# IO_Carte_Nucleo.net
KiCad netlist of a schematic drawn in Altium Designer
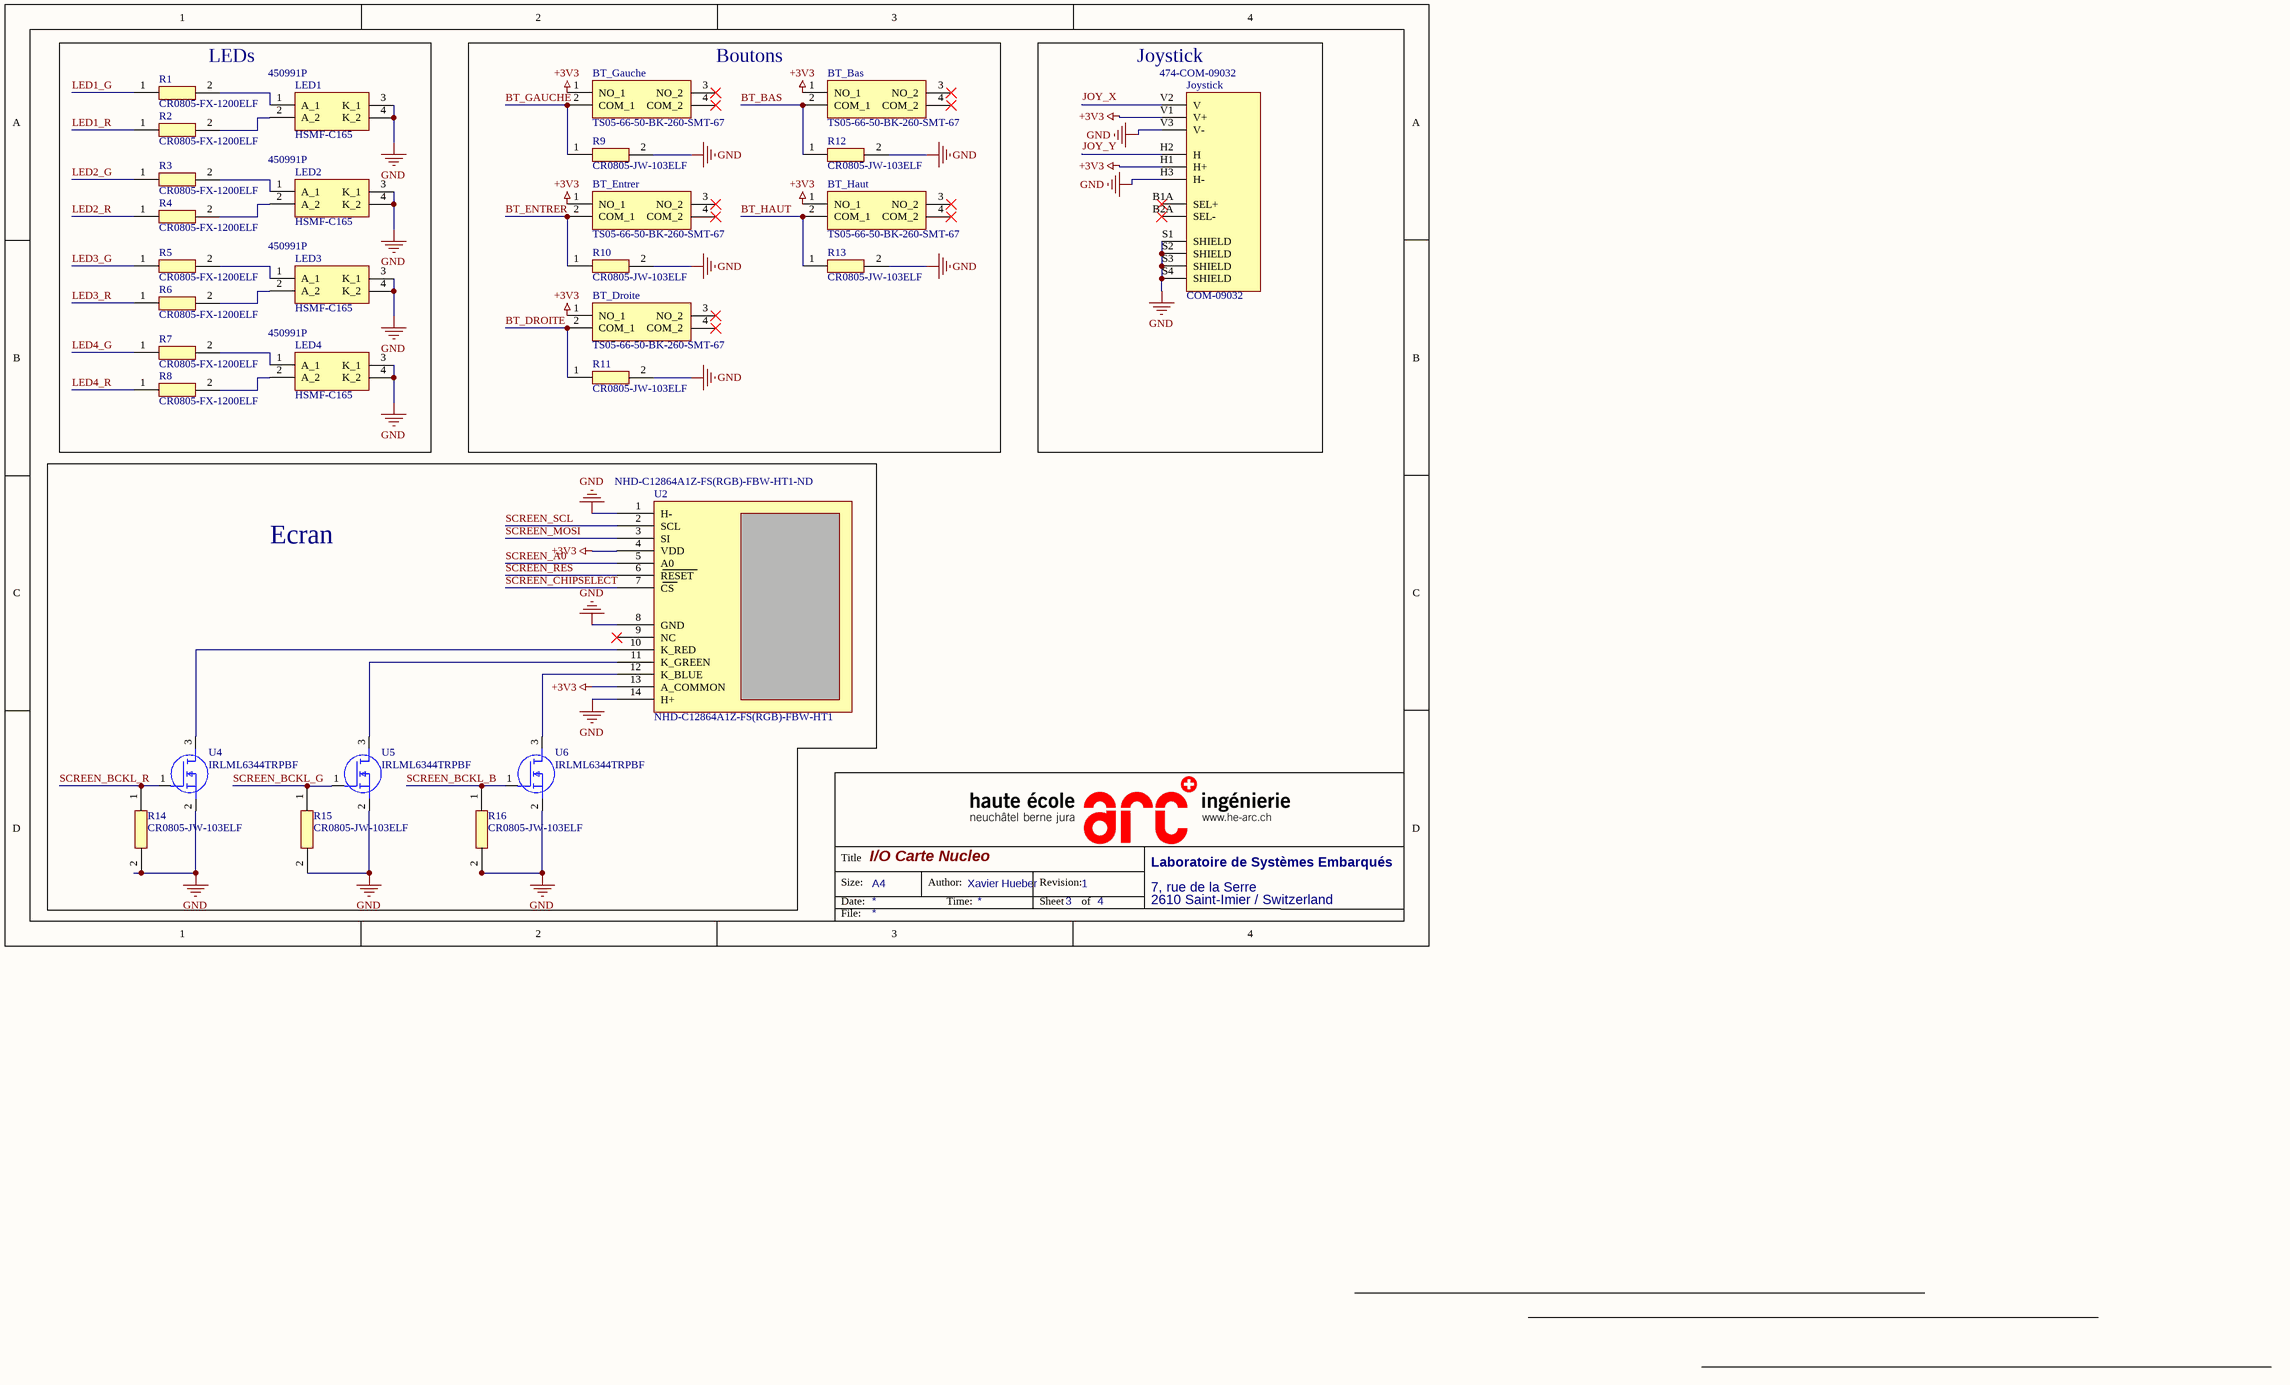
[diagram p0: IO_Carte_Nucleo.SchDoc]

(export (version "E")
  (design (tool "Eeschema 10.0.6"))
  (components
    (comp (ref "BT_Bas")
      (value "TS05-66-50-BK-260-SMT-67")
      (footprint "SamacSys:TS056650BK260SMT67")
      (description "6 x 6 mm, 4.3 ~ 8 mm Actuator Height, 100 ~ 260 gf, Surface Mount, IP67, SPST, Tactile Switch")
      (libsource (lib "*") (part "TS05-66-50-BK-260-SMT-67"))
    )
    (comp (ref "BT_Droite")
      (value "TS05-66-50-BK-260-SMT-67")
      (footprint "SamacSys:TS056650BK260SMT67")
      (description "6 x 6 mm, 4.3 ~ 8 mm Actuator Height, 100 ~ 260 gf, Surface Mount, IP67, SPST, Tactile Switch")
      (libsource (lib "*") (part "TS05-66-50-BK-260-SMT-67"))
    )
    (comp (ref "BT_Entrer")
      (value "TS05-66-50-BK-260-SMT-67")
      (footprint "SamacSys:TS056650BK260SMT67")
      (description "6 x 6 mm, 4.3 ~ 8 mm Actuator Height, 100 ~ 260 gf, Surface Mount, IP67, SPST, Tactile Switch")
      (libsource (lib "*") (part "TS05-66-50-BK-260-SMT-67"))
    )
    (comp (ref "BT_Gauche")
      (value "TS05-66-50-BK-260-SMT-67")
      (footprint "SamacSys:TS056650BK260SMT67")
      (description "6 x 6 mm, 4.3 ~ 8 mm Actuator Height, 100 ~ 260 gf, Surface Mount, IP67, SPST, Tactile Switch")
      (libsource (lib "*") (part "TS05-66-50-BK-260-SMT-67"))
    )
    (comp (ref "BT_Haut")
      (value "TS05-66-50-BK-260-SMT-67")
      (footprint "SamacSys:TS056650BK260SMT67")
      (description "6 x 6 mm, 4.3 ~ 8 mm Actuator Height, 100 ~ 260 gf, Surface Mount, IP67, SPST, Tactile Switch")
      (libsource (lib "*") (part "TS05-66-50-BK-260-SMT-67"))
    )
    (comp (ref "Joystick")
      (value "COM-09032")
      (footprint "XDCR_COM-09032")
      (description "Thumb Joystick")
      (fields (field (name "SUPPLIER PART NUMBER 1") "474-COM-09032"))
      (libsource (lib "COM-09032") (part "COM-09032"))
    )
    (comp (ref "LED1")
      (value "HSMF-C165")
      (footprint "SamacSys:HSMF-C163")
      (description "Standard LEDs - SMD Grn/Red Bi-Color")
      (fields
        (field (name "MOUSER2 PART NUMBER") "630-HSMF-C165")
        (field (name "SUPPLIER PART NUMBER 1") "450991P")
      )
      (libsource (lib "*") (part "HSMF-C165"))
    )
    (comp (ref "LED2")
      (value "HSMF-C165")
      (footprint "SamacSys:HSMF-C163")
      (description "Standard LEDs - SMD Grn/Red Bi-Color")
      (fields
        (field (name "MOUSER2 PART NUMBER") "630-HSMF-C165")
        (field (name "SUPPLIER PART NUMBER 1") "450991P")
      )
      (libsource (lib "*") (part "HSMF-C165"))
    )
    (comp (ref "LED3")
      (value "HSMF-C165")
      (footprint "SamacSys:HSMF-C163")
      (description "Standard LEDs - SMD Grn/Red Bi-Color")
      (fields
        (field (name "MOUSER2 PART NUMBER") "630-HSMF-C165")
        (field (name "SUPPLIER PART NUMBER 1") "450991P")
      )
      (libsource (lib "*") (part "HSMF-C165"))
    )
    (comp (ref "LED4")
      (value "HSMF-C165")
      (footprint "SamacSys:HSMF-C163")
      (description "Standard LEDs - SMD Grn/Red Bi-Color")
      (fields
        (field (name "MOUSER2 PART NUMBER") "630-HSMF-C165")
        (field (name "SUPPLIER PART NUMBER 1") "450991P")
      )
      (libsource (lib "*") (part "HSMF-C165"))
    )
    (comp (ref "R1")
      (value "CR0805-FX-1200ELF")
      (footprint "SamacSys:RESC2012X60N")
      (description "Res Thick Film 0805 120 Ohm 1% 1/8W ±100ppm/°C Molded SMD SMD Paper Tape on Plastic Reel")
      (libsource (lib "*") (part "CR0805-FX-1200ELF"))
    )
    (comp (ref "R2")
      (value "CR0805-FX-1200ELF")
      (footprint "SamacSys:RESC2012X60N")
      (description "Res Thick Film 0805 120 Ohm 1% 1/8W ±100ppm/°C Molded SMD SMD Paper Tape on Plastic Reel")
      (libsource (lib "*") (part "CR0805-FX-1200ELF"))
    )
    (comp (ref "R3")
      (value "CR0805-FX-1200ELF")
      (footprint "SamacSys:RESC2012X60N")
      (description "Res Thick Film 0805 120 Ohm 1% 1/8W ±100ppm/°C Molded SMD SMD Paper Tape on Plastic Reel")
      (libsource (lib "*") (part "CR0805-FX-1200ELF"))
    )
    (comp (ref "R4")
      (value "CR0805-FX-1200ELF")
      (footprint "SamacSys:RESC2012X60N")
      (description "Res Thick Film 0805 120 Ohm 1% 1/8W ±100ppm/°C Molded SMD SMD Paper Tape on Plastic Reel")
      (libsource (lib "*") (part "CR0805-FX-1200ELF"))
    )
    (comp (ref "R5")
      (value "CR0805-FX-1200ELF")
      (footprint "SamacSys:RESC2012X60N")
      (description "Res Thick Film 0805 120 Ohm 1% 1/8W ±100ppm/°C Molded SMD SMD Paper Tape on Plastic Reel")
      (libsource (lib "*") (part "CR0805-FX-1200ELF"))
    )
    (comp (ref "R6")
      (value "CR0805-FX-1200ELF")
      (footprint "SamacSys:RESC2012X60N")
      (description "Res Thick Film 0805 120 Ohm 1% 1/8W ±100ppm/°C Molded SMD SMD Paper Tape on Plastic Reel")
      (libsource (lib "*") (part "CR0805-FX-1200ELF"))
    )
    (comp (ref "R7")
      (value "CR0805-FX-1200ELF")
      (footprint "SamacSys:RESC2012X60N")
      (description "Res Thick Film 0805 120 Ohm 1% 1/8W ±100ppm/°C Molded SMD SMD Paper Tape on Plastic Reel")
      (libsource (lib "*") (part "CR0805-FX-1200ELF"))
    )
    (comp (ref "R8")
      (value "CR0805-FX-1200ELF")
      (footprint "SamacSys:RESC2012X60N")
      (description "Res Thick Film 0805 120 Ohm 1% 1/8W ±100ppm/°C Molded SMD SMD Paper Tape on Plastic Reel")
      (libsource (lib "*") (part "CR0805-FX-1200ELF"))
    )
    (comp (ref "R9")
      (value "CR0805-JW-103ELF")
      (footprint "SamacSys:RESC2012X60N")
      (libsource (lib "*") (part "CR0805-JW-103ELF"))
    )
    (comp (ref "R10")
      (value "CR0805-JW-103ELF")
      (footprint "SamacSys:RESC2012X60N")
      (libsource (lib "*") (part "CR0805-JW-103ELF"))
    )
    (comp (ref "R11")
      (value "CR0805-JW-103ELF")
      (footprint "SamacSys:RESC2012X60N")
      (libsource (lib "*") (part "CR0805-JW-103ELF"))
    )
    (comp (ref "R12")
      (value "CR0805-JW-103ELF")
      (footprint "SamacSys:RESC2012X60N")
      (libsource (lib "*") (part "CR0805-JW-103ELF"))
    )
    (comp (ref "R13")
      (value "CR0805-JW-103ELF")
      (footprint "SamacSys:RESC2012X60N")
      (libsource (lib "*") (part "CR0805-JW-103ELF"))
    )
    (comp (ref "R14")
      (value "CR0805-JW-103ELF")
      (footprint "SamacSys:RESC2012X60N")
      (libsource (lib "") (part "CR0805-JW-103ELF_1"))
    )
    (comp (ref "R15")
      (value "CR0805-JW-103ELF")
      (footprint "SamacSys:RESC2012X60N")
      (libsource (lib "") (part "CR0805-JW-103ELF_1"))
    )
    (comp (ref "R16")
      (value "CR0805-JW-103ELF")
      (footprint "SamacSys:RESC2012X60N")
      (libsource (lib "") (part "CR0805-JW-103ELF_1"))
    )
    (comp (ref "U2")
      (value "NHD-C12864A1Z-FS(RGB)-FBW-HT1")
      (footprint "NHD-C12864A1Z-FS(RGB)-FBW-HT1")
      (description "LCD COG GRAPH 128X64 RGB BKLT")
      (fields (field (name "SUPPLIER PART NUMBER 1") "NHD-C12864A1Z-FS(RGB)-FBW-HT1-ND"))
      (libsource (lib "MesComposants") (part "NHD-C12864A1Z-FS(RGB)-FBW-HT1"))
    )
    (comp (ref "U4")
      (value "IRLML6344TRPBF")
      (footprint "SamacSys:SOT95P237X112-3N")
      (description "MOSFET (N-Channel)")
      (fields (field (name "MOUSER2 PART NUMBER") "942-IRLML6344TRPBF"))
      (libsource (lib "*") (part "IRLML6344TRPBF"))
    )
    (comp (ref "U5")
      (value "IRLML6344TRPBF")
      (footprint "SamacSys:SOT95P237X112-3N")
      (description "MOSFET (N-Channel)")
      (fields (field (name "MOUSER2 PART NUMBER") "942-IRLML6344TRPBF"))
      (libsource (lib "*") (part "IRLML6344TRPBF"))
    )
    (comp (ref "U6")
      (value "IRLML6344TRPBF")
      (footprint "SamacSys:SOT95P237X112-3N")
      (description "MOSFET (N-Channel)")
      (fields (field (name "MOUSER2 PART NUMBER") "942-IRLML6344TRPBF"))
      (libsource (lib "*") (part "IRLML6344TRPBF"))
    )
  )
  (nets
    (net (code "1") (name "+3V3") (class "Default")
      (node (ref "BT_Bas") (pin "1") (pinfunction "NO_1_1") (pintype "passive"))
      (node (ref "BT_Droite") (pin "1") (pinfunction "NO_1_1") (pintype "passive"))
      (node (ref "BT_Entrer") (pin "1") (pinfunction "NO_1_1") (pintype "passive"))
      (node (ref "BT_Gauche") (pin "1") (pinfunction "NO_1_1") (pintype "passive"))
      (node (ref "BT_Haut") (pin "1") (pinfunction "NO_1_1") (pintype "passive"))
      (node (ref "Joystick") (pin "H1") (pinfunction "H+_H1") (pintype "passive"))
      (node (ref "Joystick") (pin "V1") (pinfunction "V+_V1") (pintype "passive"))
      (node (ref "U2") (pin "13") (pinfunction "A_COMMON_13") (pintype "passive"))
      (node (ref "U2") (pin "4") (pinfunction "VDD_4") (pintype "passive"))
    )
    (net (code "2") (name "/BT_BAS") (class "Default")
      (node (ref "BT_Bas") (pin "2") (pinfunction "COM_1_2") (pintype "passive"))
      (node (ref "R12") (pin "1") (pinfunction "1_1") (pintype "passive"))
    )
    (net (code "3") (name "/BT_DROITE") (class "Default")
      (node (ref "BT_Droite") (pin "2") (pinfunction "COM_1_2") (pintype "passive"))
      (node (ref "R11") (pin "1") (pinfunction "1_1") (pintype "passive"))
    )
    (net (code "4") (name "/BT_ENTRER") (class "Default")
      (node (ref "BT_Entrer") (pin "2") (pinfunction "COM_1_2") (pintype "passive"))
      (node (ref "R10") (pin "1") (pinfunction "1_1") (pintype "passive"))
    )
    (net (code "5") (name "/BT_GAUCHE") (class "Default")
      (node (ref "BT_Gauche") (pin "2") (pinfunction "COM_1_2") (pintype "passive"))
      (node (ref "R9") (pin "1") (pinfunction "1_1") (pintype "passive"))
    )
    (net (code "6") (name "/BT_HAUT") (class "Default")
      (node (ref "BT_Haut") (pin "2") (pinfunction "COM_1_2") (pintype "passive"))
      (node (ref "R13") (pin "1") (pinfunction "1_1") (pintype "passive"))
    )
    (net (code "7") (name "/JOY_X") (class "Default")
      (node (ref "Joystick") (pin "V2") (pinfunction "V_V2") (pintype "passive"))
    )
    (net (code "8") (name "/JOY_Y") (class "Default")
      (node (ref "Joystick") (pin "H2") (pinfunction "H_H2") (pintype "passive"))
    )
    (net (code "9") (name "/LED1_G") (class "Default")
      (node (ref "R1") (pin "1") (pinfunction "1_1") (pintype "passive"))
    )
    (net (code "10") (name "/LED1_R") (class "Default")
      (node (ref "R2") (pin "1") (pinfunction "1_1") (pintype "passive"))
    )
    (net (code "11") (name "/LED2_G") (class "Default")
      (node (ref "R3") (pin "1") (pinfunction "1_1") (pintype "passive"))
    )
    (net (code "12") (name "/LED2_R") (class "Default")
      (node (ref "R4") (pin "1") (pinfunction "1_1") (pintype "passive"))
    )
    (net (code "13") (name "/LED3_G") (class "Default")
      (node (ref "R5") (pin "1") (pinfunction "1_1") (pintype "passive"))
    )
    (net (code "14") (name "/LED3_R") (class "Default")
      (node (ref "R6") (pin "1") (pinfunction "1_1") (pintype "passive"))
    )
    (net (code "15") (name "/LED4_G") (class "Default")
      (node (ref "R7") (pin "1") (pinfunction "1_1") (pintype "passive"))
    )
    (net (code "16") (name "/LED4_R") (class "Default")
      (node (ref "R8") (pin "1") (pinfunction "1_1") (pintype "passive"))
    )
    (net (code "17") (name "/SCREEN_A0") (class "Default")
      (node (ref "U2") (pin "5") (pinfunction "A0_5") (pintype "passive"))
    )
    (net (code "18") (name "/SCREEN_BCKL_B") (class "Default")
      (node (ref "R16") (pin "1") (pinfunction "1_1") (pintype "passive"))
      (node (ref "U6") (pin "1") (pinfunction "G_1") (pintype "passive"))
    )
    (net (code "19") (name "/SCREEN_BCKL_G") (class "Default")
      (node (ref "R15") (pin "1") (pinfunction "1_1") (pintype "passive"))
      (node (ref "U5") (pin "1") (pinfunction "G_1") (pintype "passive"))
    )
    (net (code "20") (name "/SCREEN_BCKL_R") (class "Default")
      (node (ref "R14") (pin "1") (pinfunction "1_1") (pintype "passive"))
      (node (ref "U4") (pin "1") (pinfunction "G_1") (pintype "passive"))
    )
    (net (code "21") (name "/SCREEN_CHIPSELECT") (class "Default")
      (node (ref "U2") (pin "7") (pinfunction "CS_7") (pintype "passive"))
    )
    (net (code "22") (name "/SCREEN_MOSI") (class "Default")
      (node (ref "U2") (pin "3") (pinfunction "SI_3") (pintype "passive"))
    )
    (net (code "23") (name "/SCREEN_RES") (class "Default")
      (node (ref "U2") (pin "6") (pinfunction "RESET_6") (pintype "passive"))
    )
    (net (code "24") (name "/SCREEN_SCL") (class "Default")
      (node (ref "U2") (pin "2") (pinfunction "SCL_2") (pintype "passive"))
    )
    (net (code "25") (name "GND") (class "Default")
      (node (ref "Joystick") (pin "H3") (pinfunction "H-_H3") (pintype "passive"))
      (node (ref "Joystick") (pin "S1") (pinfunction "SHIELD_S1") (pintype "passive"))
      (node (ref "Joystick") (pin "S2") (pinfunction "SHIELD_S2") (pintype "passive"))
      (node (ref "Joystick") (pin "S3") (pinfunction "SHIELD_S3") (pintype "passive"))
      (node (ref "Joystick") (pin "S4") (pinfunction "SHIELD_S4") (pintype "passive"))
      (node (ref "Joystick") (pin "V3") (pinfunction "V-_V3") (pintype "passive"))
      (node (ref "LED1") (pin "3") (pinfunction "K_1_3") (pintype "passive"))
      (node (ref "LED1") (pin "4") (pinfunction "K_2_4") (pintype "passive"))
      (node (ref "LED2") (pin "3") (pinfunction "K_1_3") (pintype "passive"))
      (node (ref "LED2") (pin "4") (pinfunction "K_2_4") (pintype "passive"))
      (node (ref "LED3") (pin "3") (pinfunction "K_1_3") (pintype "passive"))
      (node (ref "LED3") (pin "4") (pinfunction "K_2_4") (pintype "passive"))
      (node (ref "LED4") (pin "3") (pinfunction "K_1_3") (pintype "passive"))
      (node (ref "LED4") (pin "4") (pinfunction "K_2_4") (pintype "passive"))
      (node (ref "R10") (pin "2") (pinfunction "2_2") (pintype "passive"))
      (node (ref "R11") (pin "2") (pinfunction "2_2") (pintype "passive"))
      (node (ref "R12") (pin "2") (pinfunction "2_2") (pintype "passive"))
      (node (ref "R13") (pin "2") (pinfunction "2_2") (pintype "passive"))
      (node (ref "R14") (pin "2") (pinfunction "2_2") (pintype "passive"))
      (node (ref "R15") (pin "2") (pinfunction "2_2") (pintype "passive"))
      (node (ref "R16") (pin "2") (pinfunction "2_2") (pintype "passive"))
      (node (ref "R9") (pin "2") (pinfunction "2_2") (pintype "passive"))
      (node (ref "U2") (pin "1") (pinfunction "H-_1") (pintype "passive"))
      (node (ref "U2") (pin "14") (pinfunction "H+_14") (pintype "passive"))
      (node (ref "U2") (pin "8") (pinfunction "GND_8") (pintype "passive"))
      (node (ref "U4") (pin "2") (pinfunction "S_2") (pintype "passive"))
      (node (ref "U5") (pin "2") (pinfunction "S_2") (pintype "passive"))
      (node (ref "U6") (pin "2") (pinfunction "S_2") (pintype "passive"))
    )
    (net (code "26") (name "Net-(LED1-A_1)") (class "Default")
      (node (ref "LED1") (pin "1") (pinfunction "A_1_1") (pintype "passive"))
      (node (ref "R1") (pin "2") (pinfunction "2_2") (pintype "passive"))
    )
    (net (code "27") (name "Net-(LED1-A_2)") (class "Default")
      (node (ref "LED1") (pin "2") (pinfunction "A_2_2") (pintype "passive"))
      (node (ref "R2") (pin "2") (pinfunction "2_2") (pintype "passive"))
    )
    (net (code "28") (name "Net-(LED2-A_1)") (class "Default")
      (node (ref "LED2") (pin "1") (pinfunction "A_1_1") (pintype "passive"))
      (node (ref "R3") (pin "2") (pinfunction "2_2") (pintype "passive"))
    )
    (net (code "29") (name "Net-(LED2-A_2)") (class "Default")
      (node (ref "LED2") (pin "2") (pinfunction "A_2_2") (pintype "passive"))
      (node (ref "R4") (pin "2") (pinfunction "2_2") (pintype "passive"))
    )
    (net (code "30") (name "Net-(LED3-A_1)") (class "Default")
      (node (ref "LED3") (pin "1") (pinfunction "A_1_1") (pintype "passive"))
      (node (ref "R5") (pin "2") (pinfunction "2_2") (pintype "passive"))
    )
    (net (code "31") (name "Net-(LED3-A_2)") (class "Default")
      (node (ref "LED3") (pin "2") (pinfunction "A_2_2") (pintype "passive"))
      (node (ref "R6") (pin "2") (pinfunction "2_2") (pintype "passive"))
    )
    (net (code "32") (name "Net-(LED4-A_1)") (class "Default")
      (node (ref "LED4") (pin "1") (pinfunction "A_1_1") (pintype "passive"))
      (node (ref "R7") (pin "2") (pinfunction "2_2") (pintype "passive"))
    )
    (net (code "33") (name "Net-(LED4-A_2)") (class "Default")
      (node (ref "LED4") (pin "2") (pinfunction "A_2_2") (pintype "passive"))
      (node (ref "R8") (pin "2") (pinfunction "2_2") (pintype "passive"))
    )
    (net (code "34") (name "Net-(U2-K_BLUE)") (class "Default")
      (node (ref "U2") (pin "12") (pinfunction "K_BLUE_12") (pintype "passive"))
      (node (ref "U6") (pin "3") (pinfunction "D_3") (pintype "passive"))
    )
    (net (code "35") (name "Net-(U2-K_GREEN)") (class "Default")
      (node (ref "U2") (pin "11") (pinfunction "K_GREEN_11") (pintype "passive"))
      (node (ref "U5") (pin "3") (pinfunction "D_3") (pintype "passive"))
    )
    (net (code "36") (name "Net-(U2-K_RED)") (class "Default")
      (node (ref "U2") (pin "10") (pinfunction "K_RED_10") (pintype "passive"))
      (node (ref "U4") (pin "3") (pinfunction "D_3") (pintype "passive"))
    )
    (net (code "37") (name "unconnected-(BT_Bas-COM_2-Pad4)") (class "Default")
      (node (ref "BT_Bas") (pin "4") (pinfunction "COM_2_4") (pintype "passive+no_connect"))
    )
    (net (code "38") (name "unconnected-(BT_Bas-NO_2-Pad3)") (class "Default")
      (node (ref "BT_Bas") (pin "3") (pinfunction "NO_2_3") (pintype "passive+no_connect"))
    )
    (net (code "39") (name "unconnected-(BT_Droite-COM_2-Pad4)") (class "Default")
      (node (ref "BT_Droite") (pin "4") (pinfunction "COM_2_4") (pintype "passive+no_connect"))
    )
    (net (code "40") (name "unconnected-(BT_Droite-NO_2-Pad3)") (class "Default")
      (node (ref "BT_Droite") (pin "3") (pinfunction "NO_2_3") (pintype "passive+no_connect"))
    )
    (net (code "41") (name "unconnected-(BT_Entrer-COM_2-Pad4)") (class "Default")
      (node (ref "BT_Entrer") (pin "4") (pinfunction "COM_2_4") (pintype "passive+no_connect"))
    )
    (net (code "42") (name "unconnected-(BT_Entrer-NO_2-Pad3)") (class "Default")
      (node (ref "BT_Entrer") (pin "3") (pinfunction "NO_2_3") (pintype "passive+no_connect"))
    )
    (net (code "43") (name "unconnected-(BT_Gauche-COM_2-Pad4)") (class "Default")
      (node (ref "BT_Gauche") (pin "4") (pinfunction "COM_2_4") (pintype "passive+no_connect"))
    )
    (net (code "44") (name "unconnected-(BT_Gauche-NO_2-Pad3)") (class "Default")
      (node (ref "BT_Gauche") (pin "3") (pinfunction "NO_2_3") (pintype "passive+no_connect"))
    )
    (net (code "45") (name "unconnected-(BT_Haut-COM_2-Pad4)") (class "Default")
      (node (ref "BT_Haut") (pin "4") (pinfunction "COM_2_4") (pintype "passive+no_connect"))
    )
    (net (code "46") (name "unconnected-(BT_Haut-NO_2-Pad3)") (class "Default")
      (node (ref "BT_Haut") (pin "3") (pinfunction "NO_2_3") (pintype "passive+no_connect"))
    )
    (net (code "47") (name "unconnected-(Joystick-SEL+-PadB1A)") (class "Default")
      (node (ref "Joystick") (pin "B1A") (pinfunction "SEL+_B1A") (pintype "passive+no_connect"))
    )
    (net (code "48") (name "unconnected-(Joystick-SEL--PadB2A)") (class "Default")
      (node (ref "Joystick") (pin "B2A") (pinfunction "SEL-_B2A") (pintype "passive+no_connect"))
    )
    (net (code "49") (name "unconnected-(U2-NC-Pad9)") (class "Default")
      (node (ref "U2") (pin "9") (pinfunction "NC_9") (pintype "passive+no_connect"))
    )
  )
)
